# ir-pcb.net
KiCad netlist of a schematic drawn in EAGLE
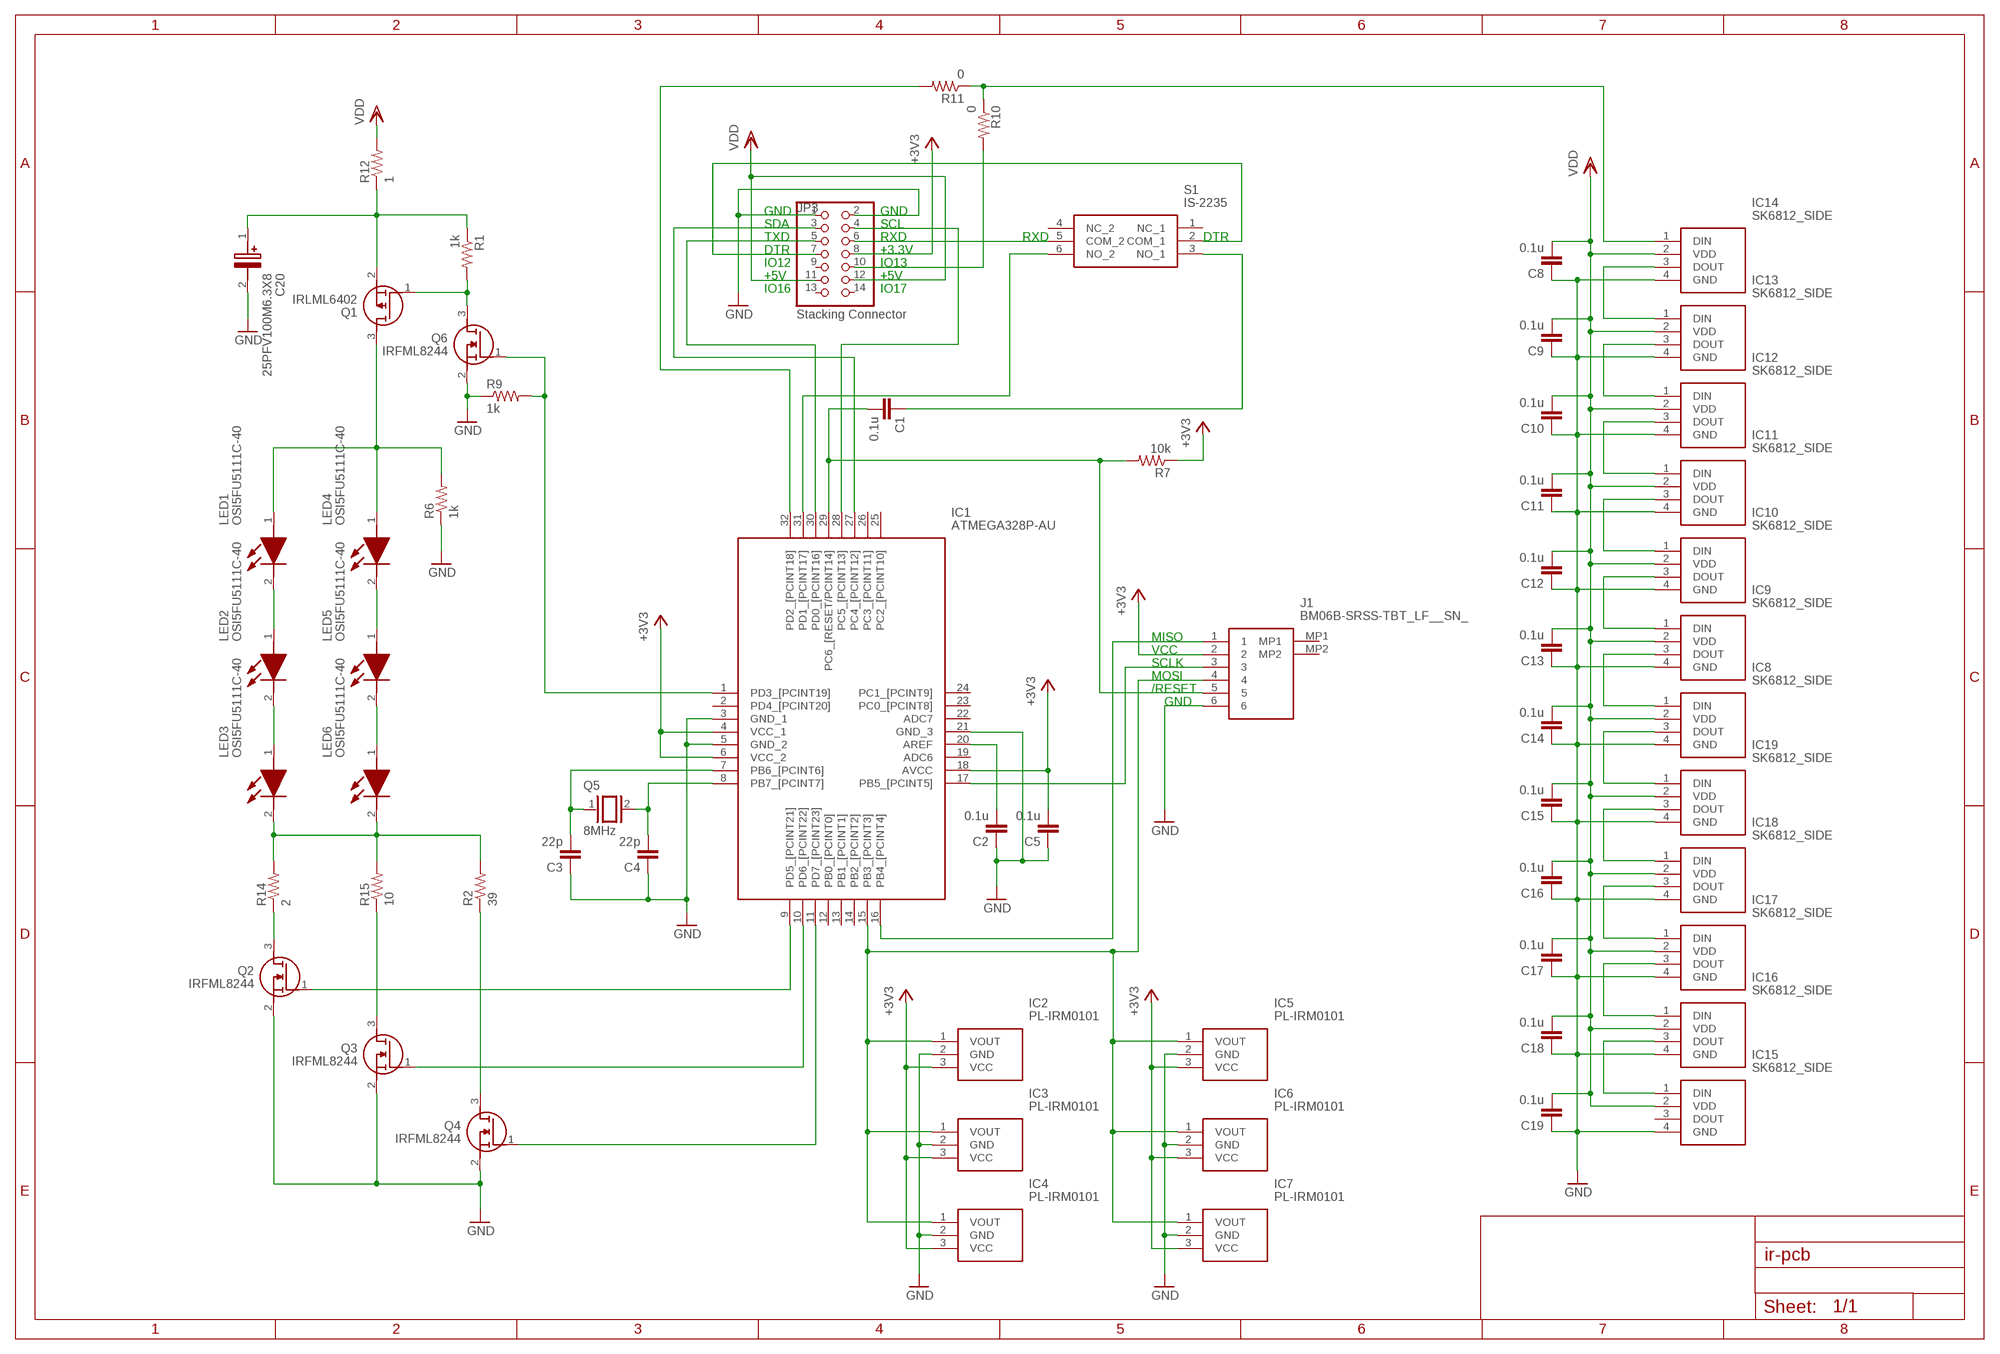
[diagram p0: schematic, sheet 1]

(export (version "E")
  (design (tool "Eeschema 10.0.6"))
  (components
    (comp (ref "C1")
      (value "0.1u")
      (footprint "eagle-import:C0603")
      (libsource (lib "eagle-import") (part "C-EUC0603"))
    )
    (comp (ref "C2")
      (value "0.1u")
      (footprint "eagle-import:C0603")
      (libsource (lib "eagle-import") (part "C-EUC0603"))
    )
    (comp (ref "C3")
      (value "22p")
      (footprint "eagle-import:C0603")
      (libsource (lib "eagle-import") (part "C-EUC0603"))
    )
    (comp (ref "C4")
      (value "22p")
      (footprint "eagle-import:C0603")
      (libsource (lib "eagle-import") (part "C-EUC0603"))
    )
    (comp (ref "C5")
      (value "0.1u")
      (footprint "eagle-import:C0603")
      (libsource (lib "eagle-import") (part "C-EUC0603"))
    )
    (comp (ref "C8")
      (value "0.1u")
      (footprint "eagle-import:C0603")
      (libsource (lib "eagle-import") (part "C-EUC0603"))
    )
    (comp (ref "C9")
      (value "0.1u")
      (footprint "eagle-import:C0603")
      (libsource (lib "eagle-import") (part "C-EUC0603"))
    )
    (comp (ref "C10")
      (value "0.1u")
      (footprint "eagle-import:C0603")
      (libsource (lib "eagle-import") (part "C-EUC0603"))
    )
    (comp (ref "C11")
      (value "0.1u")
      (footprint "eagle-import:C0603")
      (libsource (lib "eagle-import") (part "C-EUC0603"))
    )
    (comp (ref "C12")
      (value "0.1u")
      (footprint "eagle-import:C0603")
      (libsource (lib "eagle-import") (part "C-EUC0603"))
    )
    (comp (ref "C13")
      (value "0.1u")
      (footprint "eagle-import:C0603")
      (libsource (lib "eagle-import") (part "C-EUC0603"))
    )
    (comp (ref "C14")
      (value "0.1u")
      (footprint "eagle-import:C0603")
      (libsource (lib "eagle-import") (part "C-EUC0603"))
    )
    (comp (ref "C15")
      (value "0.1u")
      (footprint "eagle-import:C0603")
      (libsource (lib "eagle-import") (part "C-EUC0603"))
    )
    (comp (ref "C16")
      (value "0.1u")
      (footprint "eagle-import:C0603")
      (libsource (lib "eagle-import") (part "C-EUC0603"))
    )
    (comp (ref "C17")
      (value "0.1u")
      (footprint "eagle-import:C0603")
      (libsource (lib "eagle-import") (part "C-EUC0603"))
    )
    (comp (ref "C18")
      (value "0.1u")
      (footprint "eagle-import:C0603")
      (libsource (lib "eagle-import") (part "C-EUC0603"))
    )
    (comp (ref "C19")
      (value "0.1u")
      (footprint "eagle-import:C0603")
      (libsource (lib "eagle-import") (part "C-EUC0603"))
    )
    (comp (ref "C20")
      (value "25PFV100M6.3X8")
      (footprint "eagle-import:CAPAE660X800N")
      (fields (field (name "MOUSER_PART_NUMBER") "232-25PFV100M6.3X8"))
      (libsource (lib "eagle-import") (part "25PFV100M6.3X8"))
    )
    (comp (ref "IC1")
      (value "ATMEGA328P-AU")
      (footprint "eagle-import:QFP80P900X900X120-32N")
      (fields (field (name "MOUSER_PART_NUMBER") "556-ATMEGA328P-AU"))
      (libsource (lib "eagle-import") (part "ATMEGA328P-AU"))
    )
    (comp (ref "IC2")
      (value "PL-IRM0101")
      (footprint "eagle-import:TO254P525X740X825-3P")
      (libsource (lib "eagle-import") (part "PL-IRM0101"))
    )
    (comp (ref "IC3")
      (value "PL-IRM0101")
      (footprint "eagle-import:TO254P525X740X825-3P")
      (libsource (lib "eagle-import") (part "PL-IRM0101"))
    )
    (comp (ref "IC4")
      (value "PL-IRM0101")
      (footprint "eagle-import:TO254P525X740X825-3P")
      (libsource (lib "eagle-import") (part "PL-IRM0101"))
    )
    (comp (ref "IC5")
      (value "PL-IRM0101")
      (footprint "eagle-import:TO254P525X740X825-3P")
      (libsource (lib "eagle-import") (part "PL-IRM0101"))
    )
    (comp (ref "IC6")
      (value "PL-IRM0101")
      (footprint "eagle-import:TO254P525X740X825-3P")
      (libsource (lib "eagle-import") (part "PL-IRM0101"))
    )
    (comp (ref "IC7")
      (value "PL-IRM0101")
      (footprint "eagle-import:TO254P525X740X825-3P")
      (libsource (lib "eagle-import") (part "PL-IRM0101"))
    )
    (comp (ref "IC8")
      (value "SK6812_SIDE")
      (footprint "eagle-import:SK6812SIDE")
      (fields (field (name "MANUFACTURER_PART_NUMBER") "SK6812 SIDE"))
      (libsource (lib "eagle-import") (part "SK6812_SIDE"))
    )
    (comp (ref "IC9")
      (value "SK6812_SIDE")
      (footprint "eagle-import:SK6812SIDE")
      (fields (field (name "MANUFACTURER_PART_NUMBER") "SK6812 SIDE"))
      (libsource (lib "eagle-import") (part "SK6812_SIDE"))
    )
    (comp (ref "IC10")
      (value "SK6812_SIDE")
      (footprint "eagle-import:SK6812SIDE")
      (fields (field (name "MANUFACTURER_PART_NUMBER") "SK6812 SIDE"))
      (libsource (lib "eagle-import") (part "SK6812_SIDE"))
    )
    (comp (ref "IC11")
      (value "SK6812_SIDE")
      (footprint "eagle-import:SK6812SIDE")
      (fields (field (name "MANUFACTURER_PART_NUMBER") "SK6812 SIDE"))
      (libsource (lib "eagle-import") (part "SK6812_SIDE"))
    )
    (comp (ref "IC12")
      (value "SK6812_SIDE")
      (footprint "eagle-import:SK6812SIDE")
      (fields (field (name "MANUFACTURER_PART_NUMBER") "SK6812 SIDE"))
      (libsource (lib "eagle-import") (part "SK6812_SIDE"))
    )
    (comp (ref "IC13")
      (value "SK6812_SIDE")
      (footprint "eagle-import:SK6812SIDE")
      (fields (field (name "MANUFACTURER_PART_NUMBER") "SK6812 SIDE"))
      (libsource (lib "eagle-import") (part "SK6812_SIDE"))
    )
    (comp (ref "IC14")
      (value "SK6812_SIDE")
      (footprint "eagle-import:SK6812SIDE")
      (fields (field (name "MANUFACTURER_PART_NUMBER") "SK6812 SIDE"))
      (libsource (lib "eagle-import") (part "SK6812_SIDE"))
    )
    (comp (ref "IC15")
      (value "SK6812_SIDE")
      (footprint "eagle-import:SK6812SIDE")
      (fields (field (name "MANUFACTURER_PART_NUMBER") "SK6812 SIDE"))
      (libsource (lib "eagle-import") (part "SK6812_SIDE"))
    )
    (comp (ref "IC16")
      (value "SK6812_SIDE")
      (footprint "eagle-import:SK6812SIDE")
      (fields (field (name "MANUFACTURER_PART_NUMBER") "SK6812 SIDE"))
      (libsource (lib "eagle-import") (part "SK6812_SIDE"))
    )
    (comp (ref "IC17")
      (value "SK6812_SIDE")
      (footprint "eagle-import:SK6812SIDE")
      (fields (field (name "MANUFACTURER_PART_NUMBER") "SK6812 SIDE"))
      (libsource (lib "eagle-import") (part "SK6812_SIDE"))
    )
    (comp (ref "IC18")
      (value "SK6812_SIDE")
      (footprint "eagle-import:SK6812SIDE")
      (fields (field (name "MANUFACTURER_PART_NUMBER") "SK6812 SIDE"))
      (libsource (lib "eagle-import") (part "SK6812_SIDE"))
    )
    (comp (ref "IC19")
      (value "SK6812_SIDE")
      (footprint "eagle-import:SK6812SIDE")
      (fields (field (name "MANUFACTURER_PART_NUMBER") "SK6812 SIDE"))
      (libsource (lib "eagle-import") (part "SK6812_SIDE"))
    )
    (comp (ref "J1")
      (value "BM06B-SRSS-TBT_LF__SN_")
      (footprint "eagle-import:BM06BSRSSTBTLFSN")
      (fields (field (name "ARROW_PART_NUMBER") "BM06B-SRSS-TBT(LF)(SN)"))
      (libsource (lib "eagle-import") (part "BM06B-SRSS-TBT_LF__SN_"))
    )
    (comp (ref "JP3")
      (value "Stacking Connector")
      (footprint "eagle-import:2X07")
      (libsource (lib "eagle-import") (part "PINHD-2X7"))
    )
    (comp (ref "LED1")
      (value "OSI5FU5111C-40")
      (footprint "eagle-import:OSI5FU5111C40")
      (libsource (lib "eagle-import") (part "OSI5FU5111C-40"))
    )
    (comp (ref "LED2")
      (value "OSI5FU5111C-40")
      (footprint "eagle-import:OSI5FU5111C40")
      (libsource (lib "eagle-import") (part "OSI5FU5111C-40"))
    )
    (comp (ref "LED3")
      (value "OSI5FU5111C-40")
      (footprint "eagle-import:OSI5FU5111C40")
      (libsource (lib "eagle-import") (part "OSI5FU5111C-40"))
    )
    (comp (ref "LED4")
      (value "OSI5FU5111C-40")
      (footprint "eagle-import:OSI5FU5111C40")
      (libsource (lib "eagle-import") (part "OSI5FU5111C-40"))
    )
    (comp (ref "LED5")
      (value "OSI5FU5111C-40")
      (footprint "eagle-import:OSI5FU5111C40")
      (libsource (lib "eagle-import") (part "OSI5FU5111C-40"))
    )
    (comp (ref "LED6")
      (value "OSI5FU5111C-40")
      (footprint "eagle-import:OSI5FU5111C40")
      (libsource (lib "eagle-import") (part "OSI5FU5111C-40"))
    )
    (comp (ref "Q1")
      (value "IRLML6402")
      (footprint "eagle-import:SOT95P237X112-3N")
      (libsource (lib "eagle-import") (part "IRLML6402"))
    )
    (comp (ref "Q2")
      (value "IRFML8244")
      (footprint "eagle-import:SOT95P237X112-3N")
      (libsource (lib "eagle-import") (part "IRFML8244"))
    )
    (comp (ref "Q3")
      (value "IRFML8244")
      (footprint "eagle-import:SOT95P237X112-3N")
      (libsource (lib "eagle-import") (part "IRFML8244"))
    )
    (comp (ref "Q4")
      (value "IRFML8244")
      (footprint "eagle-import:SOT95P237X112-3N")
      (libsource (lib "eagle-import") (part "IRFML8244"))
    )
    (comp (ref "Q5")
      (value "8MHz")
      (footprint "eagle-import:QS")
      (libsource (lib "eagle-import") (part "XTAL/S"))
    )
    (comp (ref "Q6")
      (value "IRFML8244")
      (footprint "eagle-import:SOT95P237X112-3N")
      (libsource (lib "eagle-import") (part "IRFML8244"))
    )
    (comp (ref "R1")
      (value "1k")
      (footprint "eagle-import:R0603")
      (libsource (lib "eagle-import") (part "R-US_R0603"))
    )
    (comp (ref "R2")
      (value "39")
      (footprint "eagle-import:R2512W")
      (libsource (lib "eagle-import") (part "R-US_R2512W"))
    )
    (comp (ref "R6")
      (value "1k")
      (footprint "eagle-import:R0603")
      (libsource (lib "eagle-import") (part "R-US_R0603"))
    )
    (comp (ref "R7")
      (value "10k")
      (footprint "eagle-import:R0603")
      (libsource (lib "eagle-import") (part "R-US_R0603"))
    )
    (comp (ref "R9")
      (value "1k")
      (footprint "eagle-import:R0603")
      (libsource (lib "eagle-import") (part "R-US_R0603"))
    )
    (comp (ref "R10")
      (value "0")
      (footprint "eagle-import:R0603")
      (libsource (lib "eagle-import") (part "R-US_R0603"))
    )
    (comp (ref "R11")
      (value "0")
      (footprint "eagle-import:R0603")
      (libsource (lib "eagle-import") (part "R-US_R0603"))
    )
    (comp (ref "R12")
      (value "1")
      (footprint "eagle-import:R2512W")
      (libsource (lib "eagle-import") (part "R-US_R2512W"))
    )
    (comp (ref "R14")
      (value "2")
      (footprint "eagle-import:R2512W")
      (libsource (lib "eagle-import") (part "R-US_R2512W"))
    )
    (comp (ref "R15")
      (value "10")
      (footprint "eagle-import:R2512W")
      (libsource (lib "eagle-import") (part "R-US_R2512W"))
    )
    (comp (ref "S1")
      (value "IS-2235")
      (footprint "eagle-import:IS2235")
      (libsource (lib "eagle-import") (part "IS-2235"))
    )
  )
  (nets
    (net (code "1") (name "+3V3") (class "Default")
      (node (ref "C5") (pin "2") (pinfunction "2_2") (pintype "passive"))
      (node (ref "IC1") (pin "18") (pinfunction "AVCC_18") (pintype "power_in"))
      (node (ref "IC1") (pin "4") (pinfunction "VCC_1_4") (pintype "power_in"))
      (node (ref "IC1") (pin "6") (pinfunction "VCC_2_6") (pintype "power_in"))
      (node (ref "IC2") (pin "3") (pinfunction "VCC_3") (pintype "bidirectional"))
      (node (ref "IC3") (pin "3") (pinfunction "VCC_3") (pintype "bidirectional"))
      (node (ref "IC4") (pin "3") (pinfunction "VCC_3") (pintype "bidirectional"))
      (node (ref "IC5") (pin "3") (pinfunction "VCC_3") (pintype "bidirectional"))
      (node (ref "IC6") (pin "3") (pinfunction "VCC_3") (pintype "bidirectional"))
      (node (ref "IC7") (pin "3") (pinfunction "VCC_3") (pintype "bidirectional"))
      (node (ref "J1") (pin "2") (pinfunction "2_2") (pintype "bidirectional"))
      (node (ref "JP3") (pin "8") (pinfunction "8_8") (pintype "passive"))
      (node (ref "R7") (pin "1") (pinfunction "1_1") (pintype "passive"))
    )
    (net (code "2") (name "GND") (class "Default")
      (node (ref "C10") (pin "1") (pinfunction "1_1") (pintype "passive"))
      (node (ref "C11") (pin "1") (pinfunction "1_1") (pintype "passive"))
      (node (ref "C12") (pin "1") (pinfunction "1_1") (pintype "passive"))
      (node (ref "C13") (pin "1") (pinfunction "1_1") (pintype "passive"))
      (node (ref "C14") (pin "1") (pinfunction "1_1") (pintype "passive"))
      (node (ref "C15") (pin "1") (pinfunction "1_1") (pintype "passive"))
      (node (ref "C16") (pin "1") (pinfunction "1_1") (pintype "passive"))
      (node (ref "C17") (pin "1") (pinfunction "1_1") (pintype "passive"))
      (node (ref "C18") (pin "1") (pinfunction "1_1") (pintype "passive"))
      (node (ref "C19") (pin "1") (pinfunction "1_1") (pintype "passive"))
      (node (ref "C2") (pin "1") (pinfunction "1_1") (pintype "passive"))
      (node (ref "C20") (pin "2") (pinfunction "-_2") (pintype "bidirectional"))
      (node (ref "C3") (pin "1") (pinfunction "1_1") (pintype "passive"))
      (node (ref "C4") (pin "1") (pinfunction "1_1") (pintype "passive"))
      (node (ref "C5") (pin "1") (pinfunction "1_1") (pintype "passive"))
      (node (ref "C8") (pin "1") (pinfunction "1_1") (pintype "passive"))
      (node (ref "C9") (pin "1") (pinfunction "1_1") (pintype "passive"))
      (node (ref "IC1") (pin "21") (pinfunction "GND_3_21") (pintype "power_in"))
      (node (ref "IC1") (pin "3") (pinfunction "GND_1_3") (pintype "power_in"))
      (node (ref "IC1") (pin "5") (pinfunction "GND_2_5") (pintype "power_in"))
      (node (ref "IC10") (pin "4") (pinfunction "GND_4") (pintype "bidirectional"))
      (node (ref "IC11") (pin "4") (pinfunction "GND_4") (pintype "bidirectional"))
      (node (ref "IC12") (pin "4") (pinfunction "GND_4") (pintype "bidirectional"))
      (node (ref "IC13") (pin "4") (pinfunction "GND_4") (pintype "bidirectional"))
      (node (ref "IC14") (pin "4") (pinfunction "GND_4") (pintype "bidirectional"))
      (node (ref "IC15") (pin "4") (pinfunction "GND_4") (pintype "bidirectional"))
      (node (ref "IC16") (pin "4") (pinfunction "GND_4") (pintype "bidirectional"))
      (node (ref "IC17") (pin "4") (pinfunction "GND_4") (pintype "bidirectional"))
      (node (ref "IC18") (pin "4") (pinfunction "GND_4") (pintype "bidirectional"))
      (node (ref "IC19") (pin "4") (pinfunction "GND_4") (pintype "bidirectional"))
      (node (ref "IC2") (pin "2") (pinfunction "GND_2") (pintype "bidirectional"))
      (node (ref "IC3") (pin "2") (pinfunction "GND_2") (pintype "bidirectional"))
      (node (ref "IC4") (pin "2") (pinfunction "GND_2") (pintype "bidirectional"))
      (node (ref "IC5") (pin "2") (pinfunction "GND_2") (pintype "bidirectional"))
      (node (ref "IC6") (pin "2") (pinfunction "GND_2") (pintype "bidirectional"))
      (node (ref "IC7") (pin "2") (pinfunction "GND_2") (pintype "bidirectional"))
      (node (ref "IC8") (pin "4") (pinfunction "GND_4") (pintype "bidirectional"))
      (node (ref "IC9") (pin "4") (pinfunction "GND_4") (pintype "bidirectional"))
      (node (ref "J1") (pin "6") (pinfunction "6_6") (pintype "bidirectional"))
      (node (ref "JP3") (pin "1") (pinfunction "1_1") (pintype "passive"))
      (node (ref "JP3") (pin "2") (pinfunction "2_2") (pintype "passive"))
      (node (ref "Q2") (pin "2") (pinfunction "S_2") (pintype "bidirectional"))
      (node (ref "Q3") (pin "2") (pinfunction "S_2") (pintype "bidirectional"))
      (node (ref "Q4") (pin "2") (pinfunction "S_2") (pintype "bidirectional"))
      (node (ref "Q6") (pin "2") (pinfunction "S_2") (pintype "bidirectional"))
      (node (ref "R6") (pin "1") (pinfunction "1_1") (pintype "passive"))
      (node (ref "R9") (pin "1") (pinfunction "1_1") (pintype "passive"))
    )
    (net (code "3") (name "Net-(C20-+)") (class "Default")
      (node (ref "C20") (pin "1") (pinfunction "+_1") (pintype "bidirectional"))
      (node (ref "Q1") (pin "2") (pinfunction "S_2") (pintype "bidirectional"))
      (node (ref "R1") (pin "1") (pinfunction "1_1") (pintype "passive"))
      (node (ref "R12") (pin "1") (pinfunction "1_1") (pintype "passive"))
    )
    (net (code "4") (name "Net-(IC1-AREF)") (class "Default")
      (node (ref "C2") (pin "2") (pinfunction "2_2") (pintype "passive"))
      (node (ref "IC1") (pin "20") (pinfunction "AREF_20") (pintype "bidirectional"))
    )
    (net (code "5") (name "Net-(IC1-PB3_[PCINT3])") (class "Default")
      (node (ref "IC1") (pin "15") (pinfunction "PB3_[PCINT3]_15") (pintype "bidirectional"))
      (node (ref "IC2") (pin "1") (pinfunction "VOUT_1") (pintype "bidirectional"))
      (node (ref "IC3") (pin "1") (pinfunction "VOUT_1") (pintype "bidirectional"))
      (node (ref "IC4") (pin "1") (pinfunction "VOUT_1") (pintype "bidirectional"))
      (node (ref "IC5") (pin "1") (pinfunction "VOUT_1") (pintype "bidirectional"))
      (node (ref "IC6") (pin "1") (pinfunction "VOUT_1") (pintype "bidirectional"))
      (node (ref "IC7") (pin "1") (pinfunction "VOUT_1") (pintype "bidirectional"))
      (node (ref "J1") (pin "4") (pinfunction "4_4") (pintype "bidirectional"))
    )
    (net (code "6") (name "Net-(IC1-PB4_[PCINT4])") (class "Default")
      (node (ref "IC1") (pin "16") (pinfunction "PB4_[PCINT4]_16") (pintype "bidirectional"))
      (node (ref "J1") (pin "1") (pinfunction "1_1") (pintype "bidirectional"))
    )
    (net (code "7") (name "Net-(IC1-PB5_[PCINT5])") (class "Default")
      (node (ref "IC1") (pin "17") (pinfunction "PB5_[PCINT5]_17") (pintype "bidirectional"))
      (node (ref "J1") (pin "3") (pinfunction "3_3") (pintype "bidirectional"))
    )
    (net (code "8") (name "Net-(IC1-PB6_[PCINT6])") (class "Default")
      (node (ref "C3") (pin "2") (pinfunction "2_2") (pintype "passive"))
      (node (ref "IC1") (pin "7") (pinfunction "PB6_[PCINT6]_7") (pintype "bidirectional"))
      (node (ref "Q5") (pin "1") (pinfunction "1_1") (pintype "passive"))
    )
    (net (code "9") (name "Net-(IC1-PB7_[PCINT7])") (class "Default")
      (node (ref "C4") (pin "2") (pinfunction "2_2") (pintype "passive"))
      (node (ref "IC1") (pin "8") (pinfunction "PB7_[PCINT7]_8") (pintype "bidirectional"))
      (node (ref "Q5") (pin "2") (pinfunction "2_2") (pintype "passive"))
    )
    (net (code "10") (name "Net-(IC1-PC4_[PCINT12])") (class "Default")
      (node (ref "IC1") (pin "27") (pinfunction "PC4_[PCINT12]_27") (pintype "bidirectional"))
      (node (ref "JP3") (pin "3") (pinfunction "3_3") (pintype "passive"))
    )
    (net (code "11") (name "Net-(IC1-PC5_[PCINT13])") (class "Default")
      (node (ref "IC1") (pin "28") (pinfunction "PC5_[PCINT13]_28") (pintype "bidirectional"))
      (node (ref "JP3") (pin "4") (pinfunction "4_4") (pintype "passive"))
    )
    (net (code "12") (name "Net-(IC1-PC6_[RESET{slash}PCINT14])") (class "Default")
      (node (ref "C1") (pin "2") (pinfunction "2_2") (pintype "passive"))
      (node (ref "IC1") (pin "29") (pinfunction "PC6_[RESET/PCINT14]_29") (pintype "bidirectional"))
      (node (ref "J1") (pin "5") (pinfunction "5_5") (pintype "bidirectional"))
      (node (ref "R7") (pin "2") (pinfunction "2_2") (pintype "passive"))
    )
    (net (code "13") (name "Net-(IC1-PD0_[PCINT16])") (class "Default")
      (node (ref "IC1") (pin "30") (pinfunction "PD0_[PCINT16]_30") (pintype "bidirectional"))
      (node (ref "JP3") (pin "5") (pinfunction "5_5") (pintype "passive"))
    )
    (net (code "14") (name "Net-(IC1-PD1_[PCINT17])") (class "Default")
      (node (ref "IC1") (pin "31") (pinfunction "PD1_[PCINT17]_31") (pintype "bidirectional"))
      (node (ref "S1") (pin "6") (pinfunction "NO_2_6") (pintype "bidirectional"))
    )
    (net (code "15") (name "Net-(IC1-PD2_[PCINT18])") (class "Default")
      (node (ref "IC1") (pin "32") (pinfunction "PD2_[PCINT18]_32") (pintype "bidirectional"))
      (node (ref "R11") (pin "2") (pinfunction "2_2") (pintype "passive"))
    )
    (net (code "16") (name "Net-(IC1-PD3_[PCINT19])") (class "Default")
      (node (ref "IC1") (pin "1") (pinfunction "PD3_[PCINT19]_1") (pintype "bidirectional"))
      (node (ref "Q6") (pin "1") (pinfunction "G_1") (pintype "bidirectional"))
      (node (ref "R9") (pin "2") (pinfunction "2_2") (pintype "passive"))
    )
    (net (code "17") (name "Net-(IC1-PD5_[PCINT21])") (class "Default")
      (node (ref "IC1") (pin "9") (pinfunction "PD5_[PCINT21]_9") (pintype "bidirectional"))
      (node (ref "Q2") (pin "1") (pinfunction "G_1") (pintype "bidirectional"))
    )
    (net (code "18") (name "Net-(IC1-PD6_[PCINT22])") (class "Default")
      (node (ref "IC1") (pin "10") (pinfunction "PD6_[PCINT22]_10") (pintype "bidirectional"))
      (node (ref "Q3") (pin "1") (pinfunction "G_1") (pintype "bidirectional"))
    )
    (net (code "19") (name "Net-(IC1-PD7_[PCINT23])") (class "Default")
      (node (ref "IC1") (pin "11") (pinfunction "PD7_[PCINT23]_11") (pintype "bidirectional"))
      (node (ref "Q4") (pin "1") (pinfunction "G_1") (pintype "bidirectional"))
    )
    (net (code "20") (name "Net-(IC8-DIN)") (class "Default")
      (node (ref "IC8") (pin "1") (pinfunction "DIN_1") (pintype "bidirectional"))
      (node (ref "IC9") (pin "3") (pinfunction "DOUT_3") (pintype "bidirectional"))
    )
    (net (code "21") (name "Net-(IC10-DIN)") (class "Default")
      (node (ref "IC10") (pin "1") (pinfunction "DIN_1") (pintype "bidirectional"))
      (node (ref "IC11") (pin "3") (pinfunction "DOUT_3") (pintype "bidirectional"))
    )
    (net (code "22") (name "Net-(IC10-DOUT)") (class "Default")
      (node (ref "IC10") (pin "3") (pinfunction "DOUT_3") (pintype "bidirectional"))
      (node (ref "IC9") (pin "1") (pinfunction "DIN_1") (pintype "bidirectional"))
    )
    (net (code "23") (name "Net-(IC11-DIN)") (class "Default")
      (node (ref "IC11") (pin "1") (pinfunction "DIN_1") (pintype "bidirectional"))
      (node (ref "IC12") (pin "3") (pinfunction "DOUT_3") (pintype "bidirectional"))
    )
    (net (code "24") (name "Net-(IC12-DIN)") (class "Default")
      (node (ref "IC12") (pin "1") (pinfunction "DIN_1") (pintype "bidirectional"))
      (node (ref "IC13") (pin "3") (pinfunction "DOUT_3") (pintype "bidirectional"))
    )
    (net (code "25") (name "Net-(IC13-DIN)") (class "Default")
      (node (ref "IC13") (pin "1") (pinfunction "DIN_1") (pintype "bidirectional"))
      (node (ref "IC14") (pin "3") (pinfunction "DOUT_3") (pintype "bidirectional"))
    )
    (net (code "26") (name "Net-(IC14-DIN)") (class "Default")
      (node (ref "IC14") (pin "1") (pinfunction "DIN_1") (pintype "bidirectional"))
      (node (ref "R10") (pin "1") (pinfunction "1_1") (pintype "passive"))
      (node (ref "R11") (pin "1") (pinfunction "1_1") (pintype "passive"))
    )
    (net (code "27") (name "Net-(IC15-DIN)") (class "Default")
      (node (ref "IC15") (pin "1") (pinfunction "DIN_1") (pintype "bidirectional"))
      (node (ref "IC16") (pin "3") (pinfunction "DOUT_3") (pintype "bidirectional"))
    )
    (net (code "28") (name "Net-(IC16-DIN)") (class "Default")
      (node (ref "IC16") (pin "1") (pinfunction "DIN_1") (pintype "bidirectional"))
      (node (ref "IC17") (pin "3") (pinfunction "DOUT_3") (pintype "bidirectional"))
    )
    (net (code "29") (name "Net-(IC17-DIN)") (class "Default")
      (node (ref "IC17") (pin "1") (pinfunction "DIN_1") (pintype "bidirectional"))
      (node (ref "IC18") (pin "3") (pinfunction "DOUT_3") (pintype "bidirectional"))
    )
    (net (code "30") (name "Net-(IC18-DIN)") (class "Default")
      (node (ref "IC18") (pin "1") (pinfunction "DIN_1") (pintype "bidirectional"))
      (node (ref "IC19") (pin "3") (pinfunction "DOUT_3") (pintype "bidirectional"))
    )
    (net (code "31") (name "Net-(IC19-DIN)") (class "Default")
      (node (ref "IC19") (pin "1") (pinfunction "DIN_1") (pintype "bidirectional"))
      (node (ref "IC8") (pin "3") (pinfunction "DOUT_3") (pintype "bidirectional"))
    )
    (net (code "32") (name "Net-(JP3-Pad10)") (class "Default")
      (node (ref "JP3") (pin "10") (pinfunction "10_10") (pintype "passive"))
      (node (ref "R10") (pin "2") (pinfunction "2_2") (pintype "passive"))
    )
    (net (code "33") (name "Net-(LED1-A)") (class "Default")
      (node (ref "LED1") (pin "1") (pinfunction "A_1") (pintype "bidirectional"))
      (node (ref "LED4") (pin "1") (pinfunction "A_1") (pintype "bidirectional"))
      (node (ref "Q1") (pin "3") (pinfunction "D_3") (pintype "bidirectional"))
      (node (ref "R6") (pin "2") (pinfunction "2_2") (pintype "passive"))
    )
    (net (code "34") (name "Net-(LED1-K)") (class "Default")
      (node (ref "LED1") (pin "2") (pinfunction "K_2") (pintype "bidirectional"))
      (node (ref "LED2") (pin "1") (pinfunction "A_1") (pintype "bidirectional"))
    )
    (net (code "35") (name "Net-(LED2-K)") (class "Default")
      (node (ref "LED2") (pin "2") (pinfunction "K_2") (pintype "bidirectional"))
      (node (ref "LED3") (pin "1") (pinfunction "A_1") (pintype "bidirectional"))
    )
    (net (code "36") (name "Net-(LED3-K)") (class "Default")
      (node (ref "LED3") (pin "2") (pinfunction "K_2") (pintype "bidirectional"))
      (node (ref "LED6") (pin "2") (pinfunction "K_2") (pintype "bidirectional"))
      (node (ref "R14") (pin "2") (pinfunction "2_2") (pintype "passive"))
      (node (ref "R15") (pin "2") (pinfunction "2_2") (pintype "passive"))
      (node (ref "R2") (pin "2") (pinfunction "2_2") (pintype "passive"))
    )
    (net (code "37") (name "Net-(LED4-K)") (class "Default")
      (node (ref "LED4") (pin "2") (pinfunction "K_2") (pintype "bidirectional"))
      (node (ref "LED5") (pin "1") (pinfunction "A_1") (pintype "bidirectional"))
    )
    (net (code "38") (name "Net-(LED5-K)") (class "Default")
      (node (ref "LED5") (pin "2") (pinfunction "K_2") (pintype "bidirectional"))
      (node (ref "LED6") (pin "1") (pinfunction "A_1") (pintype "bidirectional"))
    )
    (net (code "39") (name "Net-(Q1-G)") (class "Default")
      (node (ref "Q1") (pin "1") (pinfunction "G_1") (pintype "bidirectional"))
      (node (ref "Q6") (pin "3") (pinfunction "D_3") (pintype "bidirectional"))
      (node (ref "R1") (pin "2") (pinfunction "2_2") (pintype "passive"))
    )
    (net (code "40") (name "Net-(Q2-D)") (class "Default")
      (node (ref "Q2") (pin "3") (pinfunction "D_3") (pintype "bidirectional"))
      (node (ref "R14") (pin "1") (pinfunction "1_1") (pintype "passive"))
    )
    (net (code "41") (name "Net-(Q3-D)") (class "Default")
      (node (ref "Q3") (pin "3") (pinfunction "D_3") (pintype "bidirectional"))
      (node (ref "R15") (pin "1") (pinfunction "1_1") (pintype "passive"))
    )
    (net (code "42") (name "Net-(Q4-D)") (class "Default")
      (node (ref "Q4") (pin "3") (pinfunction "D_3") (pintype "bidirectional"))
      (node (ref "R2") (pin "1") (pinfunction "1_1") (pintype "passive"))
    )
    (net (code "43") (name "Net-(S1-COM_1)") (class "Default")
      (node (ref "JP3") (pin "7") (pinfunction "7_7") (pintype "passive"))
      (node (ref "S1") (pin "2") (pinfunction "COM_1_2") (pintype "bidirectional"))
    )
    (net (code "44") (name "Net-(S1-COM_2)") (class "Default")
      (node (ref "JP3") (pin "6") (pinfunction "6_6") (pintype "passive"))
      (node (ref "S1") (pin "5") (pinfunction "COM_2_5") (pintype "bidirectional"))
    )
    (net (code "45") (name "Net-(S1-NO_1)") (class "Default")
      (node (ref "C1") (pin "1") (pinfunction "1_1") (pintype "passive"))
      (node (ref "S1") (pin "3") (pinfunction "NO_1_3") (pintype "bidirectional"))
    )
    (net (code "46") (name "VDD") (class "Default")
      (node (ref "C10") (pin "2") (pinfunction "2_2") (pintype "passive"))
      (node (ref "C11") (pin "2") (pinfunction "2_2") (pintype "passive"))
      (node (ref "C12") (pin "2") (pinfunction "2_2") (pintype "passive"))
      (node (ref "C13") (pin "2") (pinfunction "2_2") (pintype "passive"))
      (node (ref "C14") (pin "2") (pinfunction "2_2") (pintype "passive"))
      (node (ref "C15") (pin "2") (pinfunction "2_2") (pintype "passive"))
      (node (ref "C16") (pin "2") (pinfunction "2_2") (pintype "passive"))
      (node (ref "C17") (pin "2") (pinfunction "2_2") (pintype "passive"))
      (node (ref "C18") (pin "2") (pinfunction "2_2") (pintype "passive"))
      (node (ref "C19") (pin "2") (pinfunction "2_2") (pintype "passive"))
      (node (ref "C8") (pin "2") (pinfunction "2_2") (pintype "passive"))
      (node (ref "C9") (pin "2") (pinfunction "2_2") (pintype "passive"))
      (node (ref "IC10") (pin "2") (pinfunction "VDD_2") (pintype "bidirectional"))
      (node (ref "IC11") (pin "2") (pinfunction "VDD_2") (pintype "bidirectional"))
      (node (ref "IC12") (pin "2") (pinfunction "VDD_2") (pintype "bidirectional"))
      (node (ref "IC13") (pin "2") (pinfunction "VDD_2") (pintype "bidirectional"))
      (node (ref "IC14") (pin "2") (pinfunction "VDD_2") (pintype "bidirectional"))
      (node (ref "IC15") (pin "2") (pinfunction "VDD_2") (pintype "bidirectional"))
      (node (ref "IC16") (pin "2") (pinfunction "VDD_2") (pintype "bidirectional"))
      (node (ref "IC17") (pin "2") (pinfunction "VDD_2") (pintype "bidirectional"))
      (node (ref "IC18") (pin "2") (pinfunction "VDD_2") (pintype "bidirectional"))
      (node (ref "IC19") (pin "2") (pinfunction "VDD_2") (pintype "bidirectional"))
      (node (ref "IC8") (pin "2") (pinfunction "VDD_2") (pintype "bidirectional"))
      (node (ref "IC9") (pin "2") (pinfunction "VDD_2") (pintype "bidirectional"))
      (node (ref "JP3") (pin "11") (pinfunction "11_11") (pintype "passive"))
      (node (ref "JP3") (pin "12") (pinfunction "12_12") (pintype "passive"))
      (node (ref "R12") (pin "2") (pinfunction "2_2") (pintype "passive"))
    )
    (net (code "47") (name "unconnected-(IC1-ADC6-Pad19)") (class "Default")
      (node (ref "IC1") (pin "19") (pinfunction "ADC6_19") (pintype "bidirectional"))
    )
    (net (code "48") (name "unconnected-(IC1-ADC7-Pad22)") (class "Default")
      (node (ref "IC1") (pin "22") (pinfunction "ADC7_22") (pintype "bidirectional"))
    )
    (net (code "49") (name "unconnected-(IC1-PB0_[PCINT0]-Pad12)") (class "Default")
      (node (ref "IC1") (pin "12") (pinfunction "PB0_[PCINT0]_12") (pintype "bidirectional"))
    )
    (net (code "50") (name "unconnected-(IC1-PB1_[PCINT1]-Pad13)") (class "Default")
      (node (ref "IC1") (pin "13") (pinfunction "PB1_[PCINT1]_13") (pintype "bidirectional"))
    )
    (net (code "51") (name "unconnected-(IC1-PB2_[PCINT2]-Pad14)") (class "Default")
      (node (ref "IC1") (pin "14") (pinfunction "PB2_[PCINT2]_14") (pintype "bidirectional"))
    )
    (net (code "52") (name "unconnected-(IC1-PC0_[PCINT8]-Pad23)") (class "Default")
      (node (ref "IC1") (pin "23") (pinfunction "PC0_[PCINT8]_23") (pintype "bidirectional"))
    )
    (net (code "53") (name "unconnected-(IC1-PC1_[PCINT9]-Pad24)") (class "Default")
      (node (ref "IC1") (pin "24") (pinfunction "PC1_[PCINT9]_24") (pintype "bidirectional"))
    )
    (net (code "54") (name "unconnected-(IC1-PC2_[PCINT10]-Pad25)") (class "Default")
      (node (ref "IC1") (pin "25") (pinfunction "PC2_[PCINT10]_25") (pintype "bidirectional"))
    )
    (net (code "55") (name "unconnected-(IC1-PC3_[PCINT11]-Pad26)") (class "Default")
      (node (ref "IC1") (pin "26") (pinfunction "PC3_[PCINT11]_26") (pintype "bidirectional"))
    )
    (net (code "56") (name "unconnected-(IC1-PD4_[PCINT20]-Pad2)") (class "Default")
      (node (ref "IC1") (pin "2") (pinfunction "PD4_[PCINT20]_2") (pintype "bidirectional"))
    )
    (net (code "57") (name "unconnected-(IC15-DOUT-Pad3)") (class "Default")
      (node (ref "IC15") (pin "3") (pinfunction "DOUT_3") (pintype "bidirectional"))
    )
    (net (code "58") (name "unconnected-(J1-PadMP1)") (class "Default")
      (node (ref "J1") (pin "MP1") (pinfunction "MP1_MP1") (pintype "bidirectional"))
    )
    (net (code "59") (name "unconnected-(J1-PadMP2)") (class "Default")
      (node (ref "J1") (pin "MP2") (pinfunction "MP2_MP2") (pintype "bidirectional"))
    )
    (net (code "60") (name "unconnected-(JP3-Pad9)") (class "Default")
      (node (ref "JP3") (pin "9") (pinfunction "9_9") (pintype "passive"))
    )
    (net (code "61") (name "unconnected-(JP3-Pad13)") (class "Default")
      (node (ref "JP3") (pin "13") (pinfunction "13_13") (pintype "passive"))
    )
    (net (code "62") (name "unconnected-(JP3-Pad14)") (class "Default")
      (node (ref "JP3") (pin "14") (pinfunction "14_14") (pintype "passive"))
    )
    (net (code "63") (name "unconnected-(S1-NC_1-Pad1)") (class "Default")
      (node (ref "S1") (pin "1") (pinfunction "NC_1_1") (pintype "bidirectional"))
    )
    (net (code "64") (name "unconnected-(S1-NC_2-Pad4)") (class "Default")
      (node (ref "S1") (pin "4") (pinfunction "NC_2_4") (pintype "bidirectional"))
    )
  )
)
